# Composite_Board.net
KiCad netlist of a schematic drawn in EAGLE
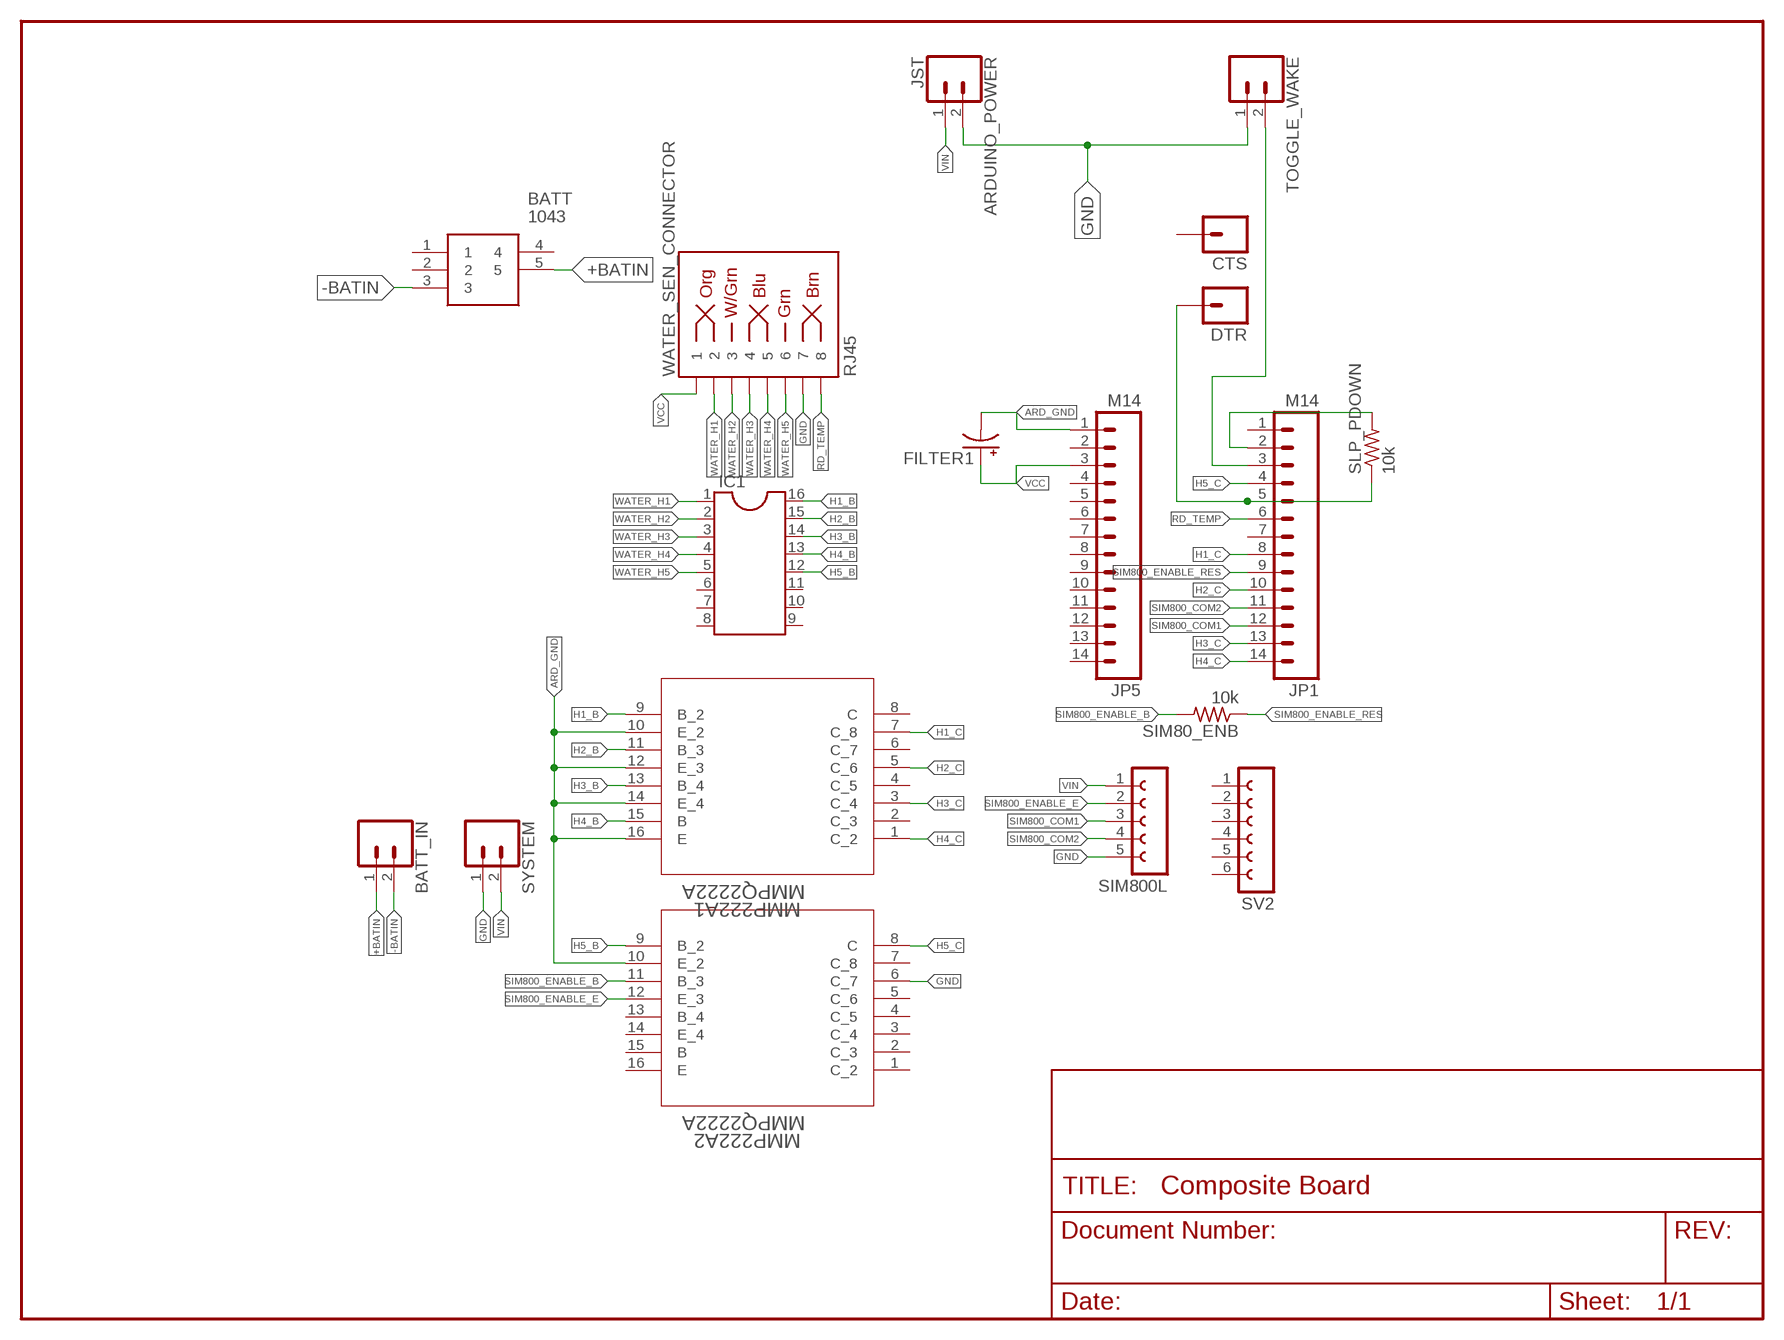
[diagram p0: schematic, sheet 1]

(export (version "E")
  (design (tool "Eeschema 10.0.6"))
  (components
    (comp (ref "ARDUINO_POWER")
      (value "JST")
      (footprint "eagle-import:1X02")
      (libsource (lib "eagle-import") (part "CONN_02"))
    )
    (comp (ref "BATT")
      (value "1043")
      (footprint "eagle-import:1043")
      (fields (field (name "MOUSER_PART_NUMBER") "534-1043"))
      (libsource (lib "eagle-import") (part "1043"))
    )
    (comp (ref "BATT_IN")
      (value "CONN_02")
      (footprint "eagle-import:1X02")
      (libsource (lib "eagle-import") (part "CONN_02"))
    )
    (comp (ref "CTS")
      (value "M01PTH")
      (footprint "eagle-import:1X01")
      (libsource (lib "eagle-import") (part "M01PTH"))
    )
    (comp (ref "DTR")
      (value "M01PTH")
      (footprint "eagle-import:1X01")
      (libsource (lib "eagle-import") (part "M01PTH"))
    )
    (comp (ref "FILTER1")
      (value "CPOL-USE2.5-5")
      (footprint "eagle-import:E2,5-5")
      (libsource (lib "eagle-import") (part "CPOL-USE2.5-5"))
    )
    (comp (ref "IC1")
      (value "DIL16S")
      (footprint "eagle-import:SOCKET-16")
      (libsource (lib "eagle-import") (part "DIL16S"))
    )
    (comp (ref "JP1")
      (value "M14")
      (footprint "eagle-import:1X14")
      (libsource (lib "eagle-import") (part "M14"))
    )
    (comp (ref "JP5")
      (value "M14")
      (footprint "eagle-import:1X14")
      (libsource (lib "eagle-import") (part "M14"))
    )
    (comp (ref "MMP222A1")
      (value "MMPQ2222A")
      (footprint "eagle-import:SO-G16")
      (libsource (lib "eagle-import") (part "MMPQ2222A"))
    )
    (comp (ref "MMP222A2")
      (value "MMPQ2222A")
      (footprint "eagle-import:SO-G16")
      (libsource (lib "eagle-import") (part "MMPQ2222A"))
    )
    (comp (ref "SIM80_ENB")
      (value "10k")
      (footprint "eagle-import:0204_5")
      (libsource (lib "eagle-import") (part "R-US_0204/5"))
    )
    (comp (ref "SIM800L")
      (value "FE05-1")
      (footprint "eagle-import:FE05-1")
      (libsource (lib "eagle-import") (part "FE05-1"))
    )
    (comp (ref "SLP_PDOWN")
      (value "10k")
      (footprint "eagle-import:0204_5")
      (libsource (lib "eagle-import") (part "R-US_0204/5"))
    )
    (comp (ref "SV2")
      (value "FE06-1")
      (footprint "eagle-import:FE06")
      (libsource (lib "eagle-import") (part "FE06-1"))
    )
    (comp (ref "SYSTEM")
      (value "CONN_02")
      (footprint "eagle-import:1X02")
      (libsource (lib "eagle-import") (part "CONN_02"))
    )
    (comp (ref "TOGGLE_WAKE")
      (value "CONN_02")
      (footprint "eagle-import:1X02")
      (libsource (lib "eagle-import") (part "CONN_02"))
    )
    (comp (ref "WATER_SEN_CONNECTOR")
      (value "RJ45")
      (footprint "eagle-import:RJ45-8")
      (libsource (lib "eagle-import") (part "RJ45-8"))
    )
  )
  (nets
    (net (code "1") (name "+BATIN") (class "Default")
      (node (ref "BATT") (pin "5") (pinfunction "5_5") (pintype "bidirectional"))
      (node (ref "BATT_IN") (pin "1") (pinfunction "1_1") (pintype "passive"))
    )
    (net (code "2") (name "-BATIN") (class "Default")
      (node (ref "BATT") (pin "3") (pinfunction "3_3") (pintype "bidirectional"))
      (node (ref "BATT_IN") (pin "2") (pinfunction "2_2") (pintype "passive"))
    )
    (net (code "3") (name "ARD_GND") (class "Default")
      (node (ref "FILTER1") (pin "-") (pinfunction "-_-") (pintype "passive"))
      (node (ref "JP5") (pin "1") (pinfunction "1_1") (pintype "passive"))
      (node (ref "MMP222A1") (pin "10") (pinfunction "E_2_10") (pintype "passive"))
      (node (ref "MMP222A1") (pin "12") (pinfunction "E_3_12") (pintype "passive"))
      (node (ref "MMP222A1") (pin "14") (pinfunction "E_4_14") (pintype "passive"))
      (node (ref "MMP222A1") (pin "16") (pinfunction "E_16") (pintype "passive"))
      (node (ref "MMP222A2") (pin "10") (pinfunction "E_2_10") (pintype "passive"))
    )
    (net (code "4") (name "GND") (class "Default")
      (node (ref "ARDUINO_POWER") (pin "2") (pinfunction "2_2") (pintype "passive"))
      (node (ref "MMP222A2") (pin "6") (pinfunction "C_7_6") (pintype "passive"))
      (node (ref "SIM800L") (pin "5") (pinfunction "5_5") (pintype "passive"))
      (node (ref "SYSTEM") (pin "1") (pinfunction "1_1") (pintype "passive"))
      (node (ref "TOGGLE_WAKE") (pin "1") (pinfunction "1_1") (pintype "passive"))
      (node (ref "WATER_SEN_CONNECTOR") (pin "7") (pinfunction "7_7") (pintype "bidirectional"))
    )
    (net (code "5") (name "H1_B") (class "Default")
      (node (ref "IC1") (pin "16") (pinfunction "16_16") (pintype "passive"))
      (node (ref "MMP222A1") (pin "9") (pinfunction "B_2_9") (pintype "passive"))
    )
    (net (code "6") (name "H1_C") (class "Default")
      (node (ref "JP1") (pin "8") (pinfunction "8_8") (pintype "passive"))
      (node (ref "MMP222A1") (pin "7") (pinfunction "C_8_7") (pintype "passive"))
    )
    (net (code "7") (name "H2_B") (class "Default")
      (node (ref "IC1") (pin "15") (pinfunction "15_15") (pintype "passive"))
      (node (ref "MMP222A1") (pin "11") (pinfunction "B_3_11") (pintype "passive"))
    )
    (net (code "8") (name "H2_C") (class "Default")
      (node (ref "JP1") (pin "10") (pinfunction "10_10") (pintype "passive"))
      (node (ref "MMP222A1") (pin "5") (pinfunction "C_6_5") (pintype "passive"))
    )
    (net (code "9") (name "H3_B") (class "Default")
      (node (ref "IC1") (pin "14") (pinfunction "14_14") (pintype "passive"))
      (node (ref "MMP222A1") (pin "13") (pinfunction "B_4_13") (pintype "passive"))
    )
    (net (code "10") (name "H3_C") (class "Default")
      (node (ref "JP1") (pin "13") (pinfunction "13_13") (pintype "passive"))
      (node (ref "MMP222A1") (pin "3") (pinfunction "C_4_3") (pintype "passive"))
    )
    (net (code "11") (name "H4_B") (class "Default")
      (node (ref "IC1") (pin "13") (pinfunction "13_13") (pintype "passive"))
      (node (ref "MMP222A1") (pin "15") (pinfunction "B_15") (pintype "passive"))
    )
    (net (code "12") (name "H4_C") (class "Default")
      (node (ref "JP1") (pin "14") (pinfunction "14_14") (pintype "passive"))
      (node (ref "MMP222A1") (pin "1") (pinfunction "C_2_1") (pintype "passive"))
    )
    (net (code "13") (name "H5_B") (class "Default")
      (node (ref "IC1") (pin "12") (pinfunction "12_12") (pintype "passive"))
      (node (ref "MMP222A2") (pin "9") (pinfunction "B_2_9") (pintype "passive"))
    )
    (net (code "14") (name "H5_C") (class "Default")
      (node (ref "JP1") (pin "4") (pinfunction "4_4") (pintype "passive"))
      (node (ref "MMP222A2") (pin "8") (pinfunction "C_8") (pintype "passive"))
    )
    (net (code "15") (name "Net-(DTR-Pad1)") (class "Default")
      (node (ref "DTR") (pin "1") (pinfunction "1_1") (pintype "passive"))
      (node (ref "JP1") (pin "5") (pinfunction "5_5") (pintype "passive"))
      (node (ref "SLP_PDOWN") (pin "1") (pinfunction "1_1") (pintype "passive"))
    )
    (net (code "16") (name "Net-(JP1-Pad2)") (class "Default")
      (node (ref "JP1") (pin "2") (pinfunction "2_2") (pintype "passive"))
      (node (ref "SLP_PDOWN") (pin "2") (pinfunction "2_2") (pintype "passive"))
    )
    (net (code "17") (name "Net-(JP1-Pad3)") (class "Default")
      (node (ref "JP1") (pin "3") (pinfunction "3_3") (pintype "passive"))
      (node (ref "TOGGLE_WAKE") (pin "2") (pinfunction "2_2") (pintype "passive"))
    )
    (net (code "18") (name "RD_TEMP") (class "Default")
      (node (ref "JP1") (pin "6") (pinfunction "6_6") (pintype "passive"))
      (node (ref "WATER_SEN_CONNECTOR") (pin "8") (pinfunction "8_8") (pintype "bidirectional"))
    )
    (net (code "19") (name "SIM800_COM1") (class "Default")
      (node (ref "JP1") (pin "12") (pinfunction "12_12") (pintype "passive"))
      (node (ref "SIM800L") (pin "3") (pinfunction "3_3") (pintype "passive"))
    )
    (net (code "20") (name "SIM800_COM2") (class "Default")
      (node (ref "JP1") (pin "11") (pinfunction "11_11") (pintype "passive"))
      (node (ref "SIM800L") (pin "4") (pinfunction "4_4") (pintype "passive"))
    )
    (net (code "21") (name "SIM800_ENABLE_B") (class "Default")
      (node (ref "MMP222A2") (pin "11") (pinfunction "B_3_11") (pintype "passive"))
      (node (ref "SIM80_ENB") (pin "2") (pinfunction "2_2") (pintype "passive"))
    )
    (net (code "22") (name "SIM800_ENABLE_E") (class "Default")
      (node (ref "MMP222A2") (pin "12") (pinfunction "E_3_12") (pintype "passive"))
      (node (ref "SIM800L") (pin "2") (pinfunction "2_2") (pintype "passive"))
    )
    (net (code "23") (name "SIM800_ENABLE_RES") (class "Default")
      (node (ref "JP1") (pin "9") (pinfunction "9_9") (pintype "passive"))
      (node (ref "SIM80_ENB") (pin "1") (pinfunction "1_1") (pintype "passive"))
    )
    (net (code "24") (name "VCC") (class "Default")
      (node (ref "FILTER1") (pin "+") (pinfunction "+_+") (pintype "passive"))
      (node (ref "JP5") (pin "3") (pinfunction "3_3") (pintype "passive"))
      (node (ref "WATER_SEN_CONNECTOR") (pin "1") (pinfunction "1_1") (pintype "bidirectional"))
    )
    (net (code "25") (name "VIN") (class "Default")
      (node (ref "ARDUINO_POWER") (pin "1") (pinfunction "1_1") (pintype "passive"))
      (node (ref "SIM800L") (pin "1") (pinfunction "1_1") (pintype "passive"))
      (node (ref "SYSTEM") (pin "2") (pinfunction "2_2") (pintype "passive"))
    )
    (net (code "26") (name "WATER_H1") (class "Default")
      (node (ref "IC1") (pin "1") (pinfunction "1_1") (pintype "passive"))
      (node (ref "WATER_SEN_CONNECTOR") (pin "2") (pinfunction "2_2") (pintype "bidirectional"))
    )
    (net (code "27") (name "WATER_H2") (class "Default")
      (node (ref "IC1") (pin "2") (pinfunction "2_2") (pintype "passive"))
      (node (ref "WATER_SEN_CONNECTOR") (pin "3") (pinfunction "3_3") (pintype "bidirectional"))
    )
    (net (code "28") (name "WATER_H3") (class "Default")
      (node (ref "IC1") (pin "3") (pinfunction "3_3") (pintype "passive"))
      (node (ref "WATER_SEN_CONNECTOR") (pin "4") (pinfunction "4_4") (pintype "bidirectional"))
    )
    (net (code "29") (name "WATER_H4") (class "Default")
      (node (ref "IC1") (pin "4") (pinfunction "4_4") (pintype "passive"))
      (node (ref "WATER_SEN_CONNECTOR") (pin "5") (pinfunction "5_5") (pintype "bidirectional"))
    )
    (net (code "30") (name "WATER_H5") (class "Default")
      (node (ref "IC1") (pin "5") (pinfunction "5_5") (pintype "passive"))
      (node (ref "WATER_SEN_CONNECTOR") (pin "6") (pinfunction "6_6") (pintype "bidirectional"))
    )
    (net (code "31") (name "unconnected-(BATT-Pad1)") (class "Default")
      (node (ref "BATT") (pin "1") (pinfunction "1_1") (pintype "bidirectional"))
    )
    (net (code "32") (name "unconnected-(BATT-Pad2)") (class "Default")
      (node (ref "BATT") (pin "2") (pinfunction "2_2") (pintype "bidirectional"))
    )
    (net (code "33") (name "unconnected-(BATT-Pad4)") (class "Default")
      (node (ref "BATT") (pin "4") (pinfunction "4_4") (pintype "bidirectional"))
    )
    (net (code "34") (name "unconnected-(CTS-Pad1)") (class "Default")
      (node (ref "CTS") (pin "1") (pinfunction "1_1") (pintype "passive"))
    )
    (net (code "35") (name "unconnected-(IC1-Pad6)") (class "Default")
      (node (ref "IC1") (pin "6") (pinfunction "6_6") (pintype "passive"))
    )
    (net (code "36") (name "unconnected-(IC1-Pad7)") (class "Default")
      (node (ref "IC1") (pin "7") (pinfunction "7_7") (pintype "passive"))
    )
    (net (code "37") (name "unconnected-(IC1-Pad8)") (class "Default")
      (node (ref "IC1") (pin "8") (pinfunction "8_8") (pintype "passive"))
    )
    (net (code "38") (name "unconnected-(IC1-Pad9)") (class "Default")
      (node (ref "IC1") (pin "9") (pinfunction "9_9") (pintype "passive"))
    )
    (net (code "39") (name "unconnected-(IC1-Pad10)") (class "Default")
      (node (ref "IC1") (pin "10") (pinfunction "10_10") (pintype "passive"))
    )
    (net (code "40") (name "unconnected-(IC1-Pad11)") (class "Default")
      (node (ref "IC1") (pin "11") (pinfunction "11_11") (pintype "passive"))
    )
    (net (code "41") (name "unconnected-(JP1-Pad1)") (class "Default")
      (node (ref "JP1") (pin "1") (pinfunction "1_1") (pintype "passive"))
    )
    (net (code "42") (name "unconnected-(JP1-Pad7)") (class "Default")
      (node (ref "JP1") (pin "7") (pinfunction "7_7") (pintype "passive"))
    )
    (net (code "43") (name "unconnected-(JP5-Pad2)") (class "Default")
      (node (ref "JP5") (pin "2") (pinfunction "2_2") (pintype "passive"))
    )
    (net (code "44") (name "unconnected-(JP5-Pad4)") (class "Default")
      (node (ref "JP5") (pin "4") (pinfunction "4_4") (pintype "passive"))
    )
    (net (code "45") (name "unconnected-(JP5-Pad5)") (class "Default")
      (node (ref "JP5") (pin "5") (pinfunction "5_5") (pintype "passive"))
    )
    (net (code "46") (name "unconnected-(JP5-Pad6)") (class "Default")
      (node (ref "JP5") (pin "6") (pinfunction "6_6") (pintype "passive"))
    )
    (net (code "47") (name "unconnected-(JP5-Pad7)") (class "Default")
      (node (ref "JP5") (pin "7") (pinfunction "7_7") (pintype "passive"))
    )
    (net (code "48") (name "unconnected-(JP5-Pad8)") (class "Default")
      (node (ref "JP5") (pin "8") (pinfunction "8_8") (pintype "passive"))
    )
    (net (code "49") (name "unconnected-(JP5-Pad9)") (class "Default")
      (node (ref "JP5") (pin "9") (pinfunction "9_9") (pintype "passive"))
    )
    (net (code "50") (name "unconnected-(JP5-Pad10)") (class "Default")
      (node (ref "JP5") (pin "10") (pinfunction "10_10") (pintype "passive"))
    )
    (net (code "51") (name "unconnected-(JP5-Pad11)") (class "Default")
      (node (ref "JP5") (pin "11") (pinfunction "11_11") (pintype "passive"))
    )
    (net (code "52") (name "unconnected-(JP5-Pad12)") (class "Default")
      (node (ref "JP5") (pin "12") (pinfunction "12_12") (pintype "passive"))
    )
    (net (code "53") (name "unconnected-(JP5-Pad13)") (class "Default")
      (node (ref "JP5") (pin "13") (pinfunction "13_13") (pintype "passive"))
    )
    (net (code "54") (name "unconnected-(JP5-Pad14)") (class "Default")
      (node (ref "JP5") (pin "14") (pinfunction "14_14") (pintype "passive"))
    )
    (net (code "55") (name "unconnected-(MMP222A1-C-Pad8)") (class "Default")
      (node (ref "MMP222A1") (pin "8") (pinfunction "C_8") (pintype "passive"))
    )
    (net (code "56") (name "unconnected-(MMP222A1-C_3-Pad2)") (class "Default")
      (node (ref "MMP222A1") (pin "2") (pinfunction "C_3_2") (pintype "passive"))
    )
    (net (code "57") (name "unconnected-(MMP222A1-C_5-Pad4)") (class "Default")
      (node (ref "MMP222A1") (pin "4") (pinfunction "C_5_4") (pintype "passive"))
    )
    (net (code "58") (name "unconnected-(MMP222A1-C_7-Pad6)") (class "Default")
      (node (ref "MMP222A1") (pin "6") (pinfunction "C_7_6") (pintype "passive"))
    )
    (net (code "59") (name "unconnected-(MMP222A2-B-Pad15)") (class "Default")
      (node (ref "MMP222A2") (pin "15") (pinfunction "B_15") (pintype "passive"))
    )
    (net (code "60") (name "unconnected-(MMP222A2-B_4-Pad13)") (class "Default")
      (node (ref "MMP222A2") (pin "13") (pinfunction "B_4_13") (pintype "passive"))
    )
    (net (code "61") (name "unconnected-(MMP222A2-C_2-Pad1)") (class "Default")
      (node (ref "MMP222A2") (pin "1") (pinfunction "C_2_1") (pintype "passive"))
    )
    (net (code "62") (name "unconnected-(MMP222A2-C_3-Pad2)") (class "Default")
      (node (ref "MMP222A2") (pin "2") (pinfunction "C_3_2") (pintype "passive"))
    )
    (net (code "63") (name "unconnected-(MMP222A2-C_4-Pad3)") (class "Default")
      (node (ref "MMP222A2") (pin "3") (pinfunction "C_4_3") (pintype "passive"))
    )
    (net (code "64") (name "unconnected-(MMP222A2-C_5-Pad4)") (class "Default")
      (node (ref "MMP222A2") (pin "4") (pinfunction "C_5_4") (pintype "passive"))
    )
    (net (code "65") (name "unconnected-(MMP222A2-C_6-Pad5)") (class "Default")
      (node (ref "MMP222A2") (pin "5") (pinfunction "C_6_5") (pintype "passive"))
    )
    (net (code "66") (name "unconnected-(MMP222A2-C_8-Pad7)") (class "Default")
      (node (ref "MMP222A2") (pin "7") (pinfunction "C_8_7") (pintype "passive"))
    )
    (net (code "67") (name "unconnected-(MMP222A2-E-Pad16)") (class "Default")
      (node (ref "MMP222A2") (pin "16") (pinfunction "E_16") (pintype "passive"))
    )
    (net (code "68") (name "unconnected-(MMP222A2-E_4-Pad14)") (class "Default")
      (node (ref "MMP222A2") (pin "14") (pinfunction "E_4_14") (pintype "passive"))
    )
    (net (code "69") (name "unconnected-(SV2-Pad1)") (class "Default")
      (node (ref "SV2") (pin "1") (pinfunction "1_1") (pintype "passive"))
    )
    (net (code "70") (name "unconnected-(SV2-Pad2)") (class "Default")
      (node (ref "SV2") (pin "2") (pinfunction "2_2") (pintype "passive"))
    )
    (net (code "71") (name "unconnected-(SV2-Pad3)") (class "Default")
      (node (ref "SV2") (pin "3") (pinfunction "3_3") (pintype "passive"))
    )
    (net (code "72") (name "unconnected-(SV2-Pad4)") (class "Default")
      (node (ref "SV2") (pin "4") (pinfunction "4_4") (pintype "passive"))
    )
    (net (code "73") (name "unconnected-(SV2-Pad5)") (class "Default")
      (node (ref "SV2") (pin "5") (pinfunction "5_5") (pintype "passive"))
    )
    (net (code "74") (name "unconnected-(SV2-Pad6)") (class "Default")
      (node (ref "SV2") (pin "6") (pinfunction "6_6") (pintype "passive"))
    )
  )
)
